# sens_less_blmd.net
KiCad netlist of a schematic drawn in EAGLE
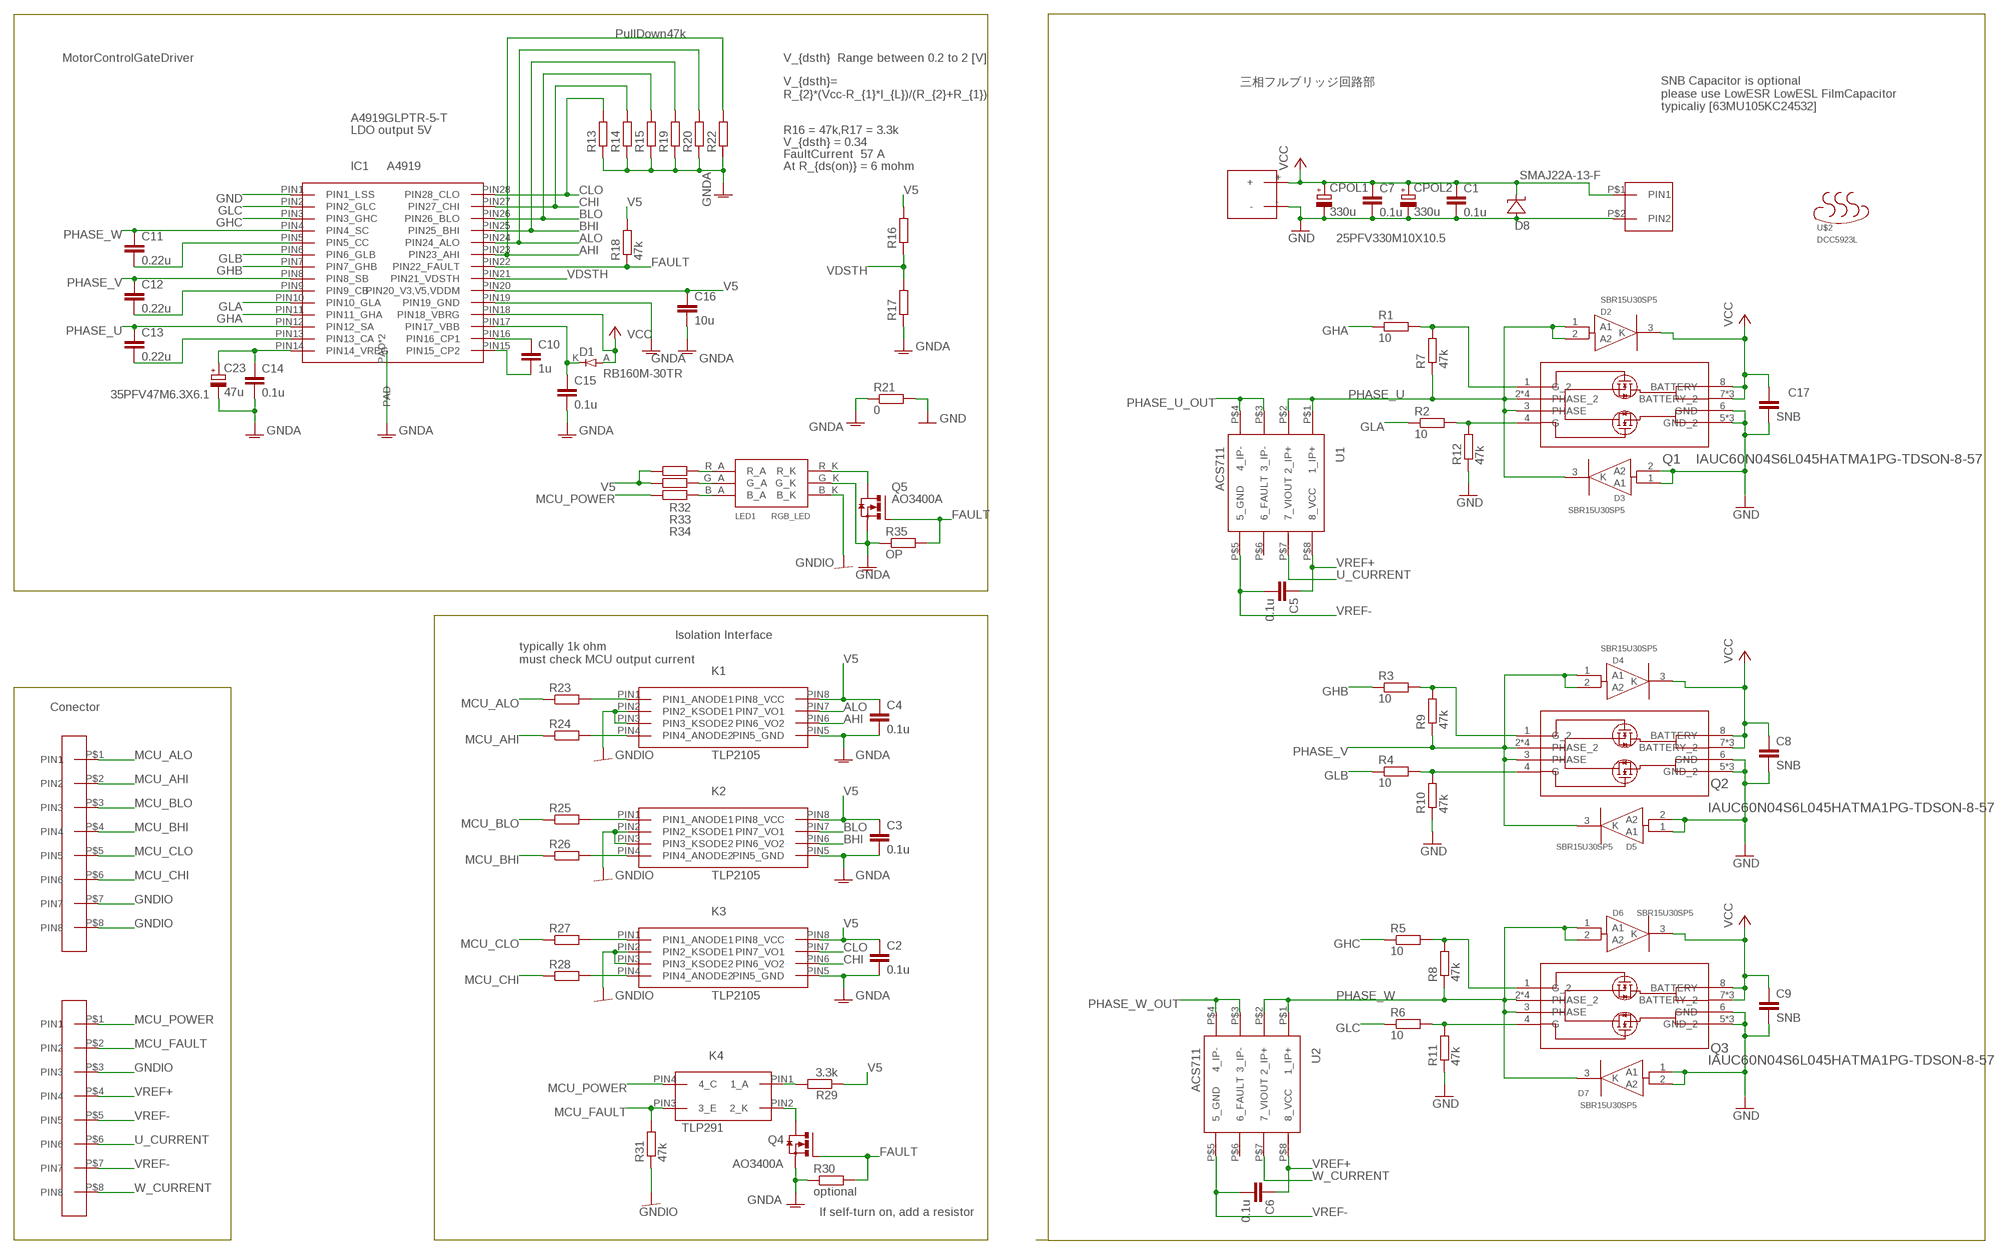
[diagram p0: schematic, sheet 1]

(export (version "E")
  (design (tool "Eeschema 10.0.6"))
  (components
    (comp (ref "C1")
      (value "0.1u")
      (footprint "eagle-import:C1608")
      (libsource (lib "eagle-import") (part "C-EUC1608"))
    )
    (comp (ref "C2")
      (value "0.1u")
      (footprint "eagle-import:C1608")
      (libsource (lib "eagle-import") (part "C-EUC1608"))
    )
    (comp (ref "C3")
      (value "0.1u")
      (footprint "eagle-import:C1608")
      (libsource (lib "eagle-import") (part "C-EUC1608"))
    )
    (comp (ref "C4")
      (value "0.1u")
      (footprint "eagle-import:C1608")
      (libsource (lib "eagle-import") (part "C-EUC1608"))
    )
    (comp (ref "C5")
      (value "0.1u")
      (footprint "eagle-import:C1608")
      (libsource (lib "eagle-import") (part "C-EUC1608"))
    )
    (comp (ref "C6")
      (value "0.1u")
      (footprint "eagle-import:C1608")
      (libsource (lib "eagle-import") (part "C-EUC1608"))
    )
    (comp (ref "C7")
      (value "0.1u")
      (footprint "eagle-import:C1608")
      (libsource (lib "eagle-import") (part "C-EUC1608"))
    )
    (comp (ref "C8")
      (value "SNB")
      (footprint "eagle-import:C4532")
      (libsource (lib "eagle-import") (part "C-EUC4532"))
    )
    (comp (ref "C9")
      (value "SNB")
      (footprint "eagle-import:C4532")
      (libsource (lib "eagle-import") (part "C-EUC4532"))
    )
    (comp (ref "C10")
      (value "1u")
      (footprint "eagle-import:C1608")
      (libsource (lib "eagle-import") (part "C-EUC1608"))
    )
    (comp (ref "C11")
      (value "0.22u")
      (footprint "eagle-import:C1608")
      (libsource (lib "eagle-import") (part "C-EUC1608"))
    )
    (comp (ref "C12")
      (value "0.22u")
      (footprint "eagle-import:C1608")
      (libsource (lib "eagle-import") (part "C-EUC1608"))
    )
    (comp (ref "C13")
      (value "0.22u")
      (footprint "eagle-import:C1608")
      (libsource (lib "eagle-import") (part "C-EUC1608"))
    )
    (comp (ref "C14")
      (value "0.1u")
      (footprint "eagle-import:C1608")
      (libsource (lib "eagle-import") (part "C-EUC1608"))
    )
    (comp (ref "C15")
      (value "0.1u")
      (footprint "eagle-import:C1608")
      (libsource (lib "eagle-import") (part "C-EUC1608"))
    )
    (comp (ref "C16")
      (value "10u")
      (footprint "eagle-import:C1608")
      (libsource (lib "eagle-import") (part "C-EUC1608"))
    )
    (comp (ref "C17")
      (value "SNB")
      (footprint "eagle-import:C4532")
      (libsource (lib "eagle-import") (part "C-EUC4532"))
    )
    (comp (ref "C23")
      (value "47u")
      (footprint "eagle-import:153CLV-0605")
      (libsource (lib "eagle-import") (part "CPOL-EU153CLV-0605"))
    )
    (comp (ref "CON1")
      (value "XH_8P")
      (footprint "eagle-import:XH_8P")
      (libsource (lib "eagle-import") (part "XH_8P"))
    )
    (comp (ref "CON2")
      (value "XH_8P")
      (footprint "eagle-import:XH_8P")
      (libsource (lib "eagle-import") (part "XH_8P"))
    )
    (comp (ref "CPOL1")
      (value "330u")
      (footprint "eagle-import:1014CAPA")
      (libsource (lib "eagle-import") (part "C_DEKAI"))
    )
    (comp (ref "CPOL2")
      (value "330u")
      (footprint "eagle-import:1014CAPA")
      (libsource (lib "eagle-import") (part "C_DEKAI"))
    )
    (comp (ref "D1")
      (value "RB160M-30TR")
      (footprint "eagle-import:SOD_123")
      (libsource (lib "eagle-import") (part "SMD_DAIOD"))
    )
    (comp (ref "D2")
      (value "SBR15U30SP5")
      (footprint "eagle-import:POWERDI_5")
      (libsource (lib "eagle-import") (part "SBR15U30SP5"))
    )
    (comp (ref "D3")
      (value "SBR15U30SP5")
      (footprint "eagle-import:POWERDI_5")
      (libsource (lib "eagle-import") (part "SBR15U30SP5"))
    )
    (comp (ref "D4")
      (value "SBR15U30SP5")
      (footprint "eagle-import:POWERDI_5")
      (libsource (lib "eagle-import") (part "SBR15U30SP5"))
    )
    (comp (ref "D5")
      (value "SBR15U30SP5")
      (footprint "eagle-import:POWERDI_5")
      (libsource (lib "eagle-import") (part "SBR15U30SP5"))
    )
    (comp (ref "D6")
      (value "SBR15U30SP5")
      (footprint "eagle-import:POWERDI_5")
      (libsource (lib "eagle-import") (part "SBR15U30SP5"))
    )
    (comp (ref "D7")
      (value "SBR15U30SP5")
      (footprint "eagle-import:POWERDI_5")
      (libsource (lib "eagle-import") (part "SBR15U30SP5"))
    )
    (comp (ref "D8")
      (value "SMAJ22A-13-F")
      (footprint "eagle-import:DO-214AC")
      (libsource (lib "eagle-import") (part "SMAJ22A-13-F"))
    )
    (comp (ref "IC1")
      (value "A4919")
      (footprint "eagle-import:TSSOP_28P_ALLEGRO_E")
      (libsource (lib "eagle-import") (part "A4919"))
    )
    (comp (ref "K1")
      (value "TLP2105")
      (footprint "eagle-import:SOP8")
      (libsource (lib "eagle-import") (part "TLP2105"))
    )
    (comp (ref "K2")
      (value "TLP2105")
      (footprint "eagle-import:SOP8")
      (libsource (lib "eagle-import") (part "TLP2105"))
    )
    (comp (ref "K3")
      (value "TLP2105")
      (footprint "eagle-import:SOP8")
      (libsource (lib "eagle-import") (part "TLP2105"))
    )
    (comp (ref "K4")
      (value "TLP291")
      (footprint "eagle-import:TLP291")
      (libsource (lib "eagle-import") (part "TLP291"))
    )
    (comp (ref "LED1")
      (value "RGB_LED")
      (footprint "eagle-import:RGB_LED")
      (libsource (lib "eagle-import") (part "RGB_LED"))
    )
    (comp (ref "Q1")
      (value "IAUC60N04S6L045HATMA1PG-TDSON-8-57")
      (footprint "eagle-import:PG-TDSON-8-57")
      (fields
        (field (name "MANUFACTURER_PART_NUMBER") "IAUC60N04S6L045HATMA1")
        (field (name "COPYRIGHT") "Copyright (C) 2024 Ultra Librarian. All rights reserved.")
      )
      (libsource (lib "eagle-import") (part "IAUC60N04S6L045HATMA1PG-TDSON-8-57"))
    )
    (comp (ref "Q2")
      (value "IAUC60N04S6L045HATMA1PG-TDSON-8-57")
      (footprint "eagle-import:PG-TDSON-8-57")
      (fields
        (field (name "MANUFACTURER_PART_NUMBER") "IAUC60N04S6L045HATMA1")
        (field (name "COPYRIGHT") "Copyright (C) 2024 Ultra Librarian. All rights reserved.")
      )
      (libsource (lib "eagle-import") (part "IAUC60N04S6L045HATMA1PG-TDSON-8-57"))
    )
    (comp (ref "Q3")
      (value "IAUC60N04S6L045HATMA1PG-TDSON-8-57")
      (footprint "eagle-import:PG-TDSON-8-57")
      (fields
        (field (name "MANUFACTURER_PART_NUMBER") "IAUC60N04S6L045HATMA1")
        (field (name "COPYRIGHT") "Copyright (C) 2024 Ultra Librarian. All rights reserved.")
      )
      (libsource (lib "eagle-import") (part "IAUC60N04S6L045HATMA1PG-TDSON-8-57"))
    )
    (comp (ref "Q4")
      (value "AO3400A")
      (footprint "eagle-import:SOT23")
      (libsource (lib "eagle-import") (part "SOT23_NFET"))
    )
    (comp (ref "Q5")
      (value "AO3400A")
      (footprint "eagle-import:SOT23")
      (libsource (lib "eagle-import") (part "SOT23_NFET"))
    )
    (comp (ref "R1")
      (value "10")
      (footprint "eagle-import:1608")
      (libsource (lib "eagle-import") (part "R_REG"))
    )
    (comp (ref "R2")
      (value "10")
      (footprint "eagle-import:1608")
      (libsource (lib "eagle-import") (part "R_REG"))
    )
    (comp (ref "R3")
      (value "10")
      (footprint "eagle-import:1608")
      (libsource (lib "eagle-import") (part "R_REG"))
    )
    (comp (ref "R4")
      (value "10")
      (footprint "eagle-import:1608")
      (libsource (lib "eagle-import") (part "R_REG"))
    )
    (comp (ref "R5")
      (value "10")
      (footprint "eagle-import:1608")
      (libsource (lib "eagle-import") (part "R_REG"))
    )
    (comp (ref "R6")
      (value "10")
      (footprint "eagle-import:1608")
      (libsource (lib "eagle-import") (part "R_REG"))
    )
    (comp (ref "R7")
      (value "47k")
      (footprint "eagle-import:1608")
      (libsource (lib "eagle-import") (part "R_REG"))
    )
    (comp (ref "R8")
      (value "47k")
      (footprint "eagle-import:1608")
      (libsource (lib "eagle-import") (part "R_REG"))
    )
    (comp (ref "R9")
      (value "47k")
      (footprint "eagle-import:1608")
      (libsource (lib "eagle-import") (part "R_REG"))
    )
    (comp (ref "R10")
      (value "47k")
      (footprint "eagle-import:1608")
      (libsource (lib "eagle-import") (part "R_REG"))
    )
    (comp (ref "R11")
      (value "47k")
      (footprint "eagle-import:1608")
      (libsource (lib "eagle-import") (part "R_REG"))
    )
    (comp (ref "R12")
      (value "47k")
      (footprint "eagle-import:1608")
      (libsource (lib "eagle-import") (part "R_REG"))
    )
    (comp (ref "R13")
      (value "R_REG")
      (footprint "eagle-import:1608")
      (libsource (lib "eagle-import") (part "R_REG"))
    )
    (comp (ref "R14")
      (value "R_REG")
      (footprint "eagle-import:1608")
      (libsource (lib "eagle-import") (part "R_REG"))
    )
    (comp (ref "R15")
      (value "R_REG")
      (footprint "eagle-import:1608")
      (libsource (lib "eagle-import") (part "R_REG"))
    )
    (comp (ref "R16")
      (value "R_REG")
      (footprint "eagle-import:1608")
      (libsource (lib "eagle-import") (part "R_REG"))
    )
    (comp (ref "R17")
      (value "R_REG")
      (footprint "eagle-import:1608")
      (libsource (lib "eagle-import") (part "R_REG"))
    )
    (comp (ref "R18")
      (value "47k")
      (footprint "eagle-import:1608")
      (libsource (lib "eagle-import") (part "R_REG"))
    )
    (comp (ref "R19")
      (value "R_REG")
      (footprint "eagle-import:1608")
      (libsource (lib "eagle-import") (part "R_REG"))
    )
    (comp (ref "R20")
      (value "R_REG")
      (footprint "eagle-import:1608")
      (libsource (lib "eagle-import") (part "R_REG"))
    )
    (comp (ref "R21")
      (value "0")
      (footprint "eagle-import:1608")
      (libsource (lib "eagle-import") (part "R_REG"))
    )
    (comp (ref "R22")
      (value "R_REG")
      (footprint "eagle-import:1608")
      (libsource (lib "eagle-import") (part "R_REG"))
    )
    (comp (ref "R23")
      (value "R_REG")
      (footprint "eagle-import:1608")
      (libsource (lib "eagle-import") (part "R_REG"))
    )
    (comp (ref "R24")
      (value "R_REG")
      (footprint "eagle-import:1608")
      (libsource (lib "eagle-import") (part "R_REG"))
    )
    (comp (ref "R25")
      (value "R_REG")
      (footprint "eagle-import:1608")
      (libsource (lib "eagle-import") (part "R_REG"))
    )
    (comp (ref "R26")
      (value "R_REG")
      (footprint "eagle-import:1608")
      (libsource (lib "eagle-import") (part "R_REG"))
    )
    (comp (ref "R27")
      (value "R_REG")
      (footprint "eagle-import:1608")
      (libsource (lib "eagle-import") (part "R_REG"))
    )
    (comp (ref "R28")
      (value "R_REG")
      (footprint "eagle-import:1608")
      (libsource (lib "eagle-import") (part "R_REG"))
    )
    (comp (ref "R29")
      (value "3.3k")
      (footprint "eagle-import:1608")
      (libsource (lib "eagle-import") (part "R_REG"))
    )
    (comp (ref "R30")
      (value "optional")
      (footprint "eagle-import:1608")
      (libsource (lib "eagle-import") (part "R_REG"))
    )
    (comp (ref "R31")
      (value "47k")
      (footprint "eagle-import:1608")
      (libsource (lib "eagle-import") (part "R_REG"))
    )
    (comp (ref "R32")
      (value "R_REG")
      (footprint "eagle-import:1608")
      (libsource (lib "eagle-import") (part "R_REG"))
    )
    (comp (ref "R33")
      (value "R_REG")
      (footprint "eagle-import:1608")
      (libsource (lib "eagle-import") (part "R_REG"))
    )
    (comp (ref "R34")
      (value "R_REG")
      (footprint "eagle-import:1608")
      (libsource (lib "eagle-import") (part "R_REG"))
    )
    (comp (ref "R35")
      (value "OP")
      (footprint "eagle-import:1608")
      (libsource (lib "eagle-import") (part "R_REG"))
    )
    (comp (ref "U$1")
      (value "XH_2P")
      (footprint "eagle-import:XH_2P")
      (libsource (lib "eagle-import") (part "XH_2P"))
    )
    (comp (ref "U$2")
      (value "DCC5923L")
      (footprint "eagle-import:DCC5923L")
      (libsource (lib "eagle-import") (part "DCC5923L"))
    )
    (comp (ref "U$22")
      (value "XT60")
      (footprint "eagle-import:XT60")
      (libsource (lib "eagle-import") (part "XT60"))
    )
    (comp (ref "U1")
      (value "ACS711")
      (footprint "eagle-import:SOIC8")
      (libsource (lib "eagle-import") (part "ACS711"))
    )
    (comp (ref "U2")
      (value "ACS711")
      (footprint "eagle-import:SOIC8")
      (libsource (lib "eagle-import") (part "ACS711"))
    )
  )
  (nets
    (net (code "1") (name "/AHI") (class "Default")
      (node (ref "IC1") (pin "PIN23") (pinfunction "PIN23_AHI_PIN23") (pintype "bidirectional"))
      (node (ref "K1") (pin "PIN6") (pinfunction "PIN6_VO2_PIN6") (pintype "bidirectional"))
      (node (ref "R22") (pin "2") (pinfunction "2_2") (pintype "passive"))
    )
    (net (code "2") (name "/ALO") (class "Default")
      (node (ref "IC1") (pin "PIN24") (pinfunction "PIN24_ALO_PIN24") (pintype "bidirectional"))
      (node (ref "K1") (pin "PIN7") (pinfunction "PIN7_VO1_PIN7") (pintype "bidirectional"))
      (node (ref "R20") (pin "2") (pinfunction "2_2") (pintype "passive"))
    )
    (net (code "3") (name "/BHI") (class "Default")
      (node (ref "IC1") (pin "PIN25") (pinfunction "PIN25_BHI_PIN25") (pintype "bidirectional"))
      (node (ref "K2") (pin "PIN6") (pinfunction "PIN6_VO2_PIN6") (pintype "bidirectional"))
      (node (ref "R19") (pin "2") (pinfunction "2_2") (pintype "passive"))
    )
    (net (code "4") (name "/BLO") (class "Default")
      (node (ref "IC1") (pin "PIN26") (pinfunction "PIN26_BLO_PIN26") (pintype "bidirectional"))
      (node (ref "K2") (pin "PIN7") (pinfunction "PIN7_VO1_PIN7") (pintype "bidirectional"))
      (node (ref "R15") (pin "2") (pinfunction "2_2") (pintype "passive"))
    )
    (net (code "5") (name "/CHI") (class "Default")
      (node (ref "IC1") (pin "PIN27") (pinfunction "PIN27_CHI_PIN27") (pintype "bidirectional"))
      (node (ref "K3") (pin "PIN6") (pinfunction "PIN6_VO2_PIN6") (pintype "bidirectional"))
      (node (ref "R14") (pin "2") (pinfunction "2_2") (pintype "passive"))
    )
    (net (code "6") (name "/CLO") (class "Default")
      (node (ref "IC1") (pin "PIN28") (pinfunction "PIN28_CLO_PIN28") (pintype "bidirectional"))
      (node (ref "K3") (pin "PIN7") (pinfunction "PIN7_VO1_PIN7") (pintype "bidirectional"))
      (node (ref "R13") (pin "2") (pinfunction "2_2") (pintype "passive"))
    )
    (net (code "7") (name "/FAULT") (class "Default")
      (node (ref "IC1") (pin "PIN22") (pinfunction "PIN22_FAULT_PIN22") (pintype "bidirectional"))
      (node (ref "Q4") (pin "PIN1") (pinfunction "PIN1_G_PIN1") (pintype "passive"))
      (node (ref "Q5") (pin "PIN1") (pinfunction "PIN1_G_PIN1") (pintype "passive"))
      (node (ref "R18") (pin "1") (pinfunction "1_1") (pintype "passive"))
      (node (ref "R30") (pin "2") (pinfunction "2_2") (pintype "passive"))
      (node (ref "R35") (pin "2") (pinfunction "2_2") (pintype "passive"))
    )
    (net (code "8") (name "/GHA") (class "Default")
      (node (ref "IC1") (pin "PIN11") (pinfunction "PIN11_GHA_PIN11") (pintype "bidirectional"))
      (node (ref "R1") (pin "1") (pinfunction "1_1") (pintype "passive"))
    )
    (net (code "9") (name "/GHB") (class "Default")
      (node (ref "IC1") (pin "PIN7") (pinfunction "PIN7_GHB_PIN7") (pintype "bidirectional"))
      (node (ref "R3") (pin "1") (pinfunction "1_1") (pintype "passive"))
    )
    (net (code "10") (name "/GHC") (class "Default")
      (node (ref "IC1") (pin "PIN3") (pinfunction "PIN3_GHC_PIN3") (pintype "bidirectional"))
      (node (ref "R5") (pin "1") (pinfunction "1_1") (pintype "passive"))
    )
    (net (code "11") (name "/GLA") (class "Default")
      (node (ref "IC1") (pin "PIN10") (pinfunction "PIN10_GLA_PIN10") (pintype "bidirectional"))
      (node (ref "R2") (pin "1") (pinfunction "1_1") (pintype "passive"))
    )
    (net (code "12") (name "/GLB") (class "Default")
      (node (ref "IC1") (pin "PIN6") (pinfunction "PIN6_GLB_PIN6") (pintype "bidirectional"))
      (node (ref "R4") (pin "1") (pinfunction "1_1") (pintype "passive"))
    )
    (net (code "13") (name "/GLC") (class "Default")
      (node (ref "IC1") (pin "PIN2") (pinfunction "PIN2_GLC_PIN2") (pintype "bidirectional"))
      (node (ref "R6") (pin "1") (pinfunction "1_1") (pintype "passive"))
    )
    (net (code "14") (name "/MCU_AHI") (class "Default")
      (node (ref "CON2") (pin "P$2") (pinfunction "PIN2_P$2") (pintype "bidirectional"))
      (node (ref "R24") (pin "1") (pinfunction "1_1") (pintype "passive"))
    )
    (net (code "15") (name "/MCU_ALO") (class "Default")
      (node (ref "CON2") (pin "P$1") (pinfunction "PIN1_P$1") (pintype "bidirectional"))
      (node (ref "R23") (pin "1") (pinfunction "1_1") (pintype "passive"))
    )
    (net (code "16") (name "/MCU_BHI") (class "Default")
      (node (ref "CON2") (pin "P$4") (pinfunction "PIN4_P$4") (pintype "bidirectional"))
      (node (ref "R26") (pin "1") (pinfunction "1_1") (pintype "passive"))
    )
    (net (code "17") (name "/MCU_BLO") (class "Default")
      (node (ref "CON2") (pin "P$3") (pinfunction "PIN3_P$3") (pintype "bidirectional"))
      (node (ref "R25") (pin "1") (pinfunction "1_1") (pintype "passive"))
    )
    (net (code "18") (name "/MCU_CHI") (class "Default")
      (node (ref "CON2") (pin "P$6") (pinfunction "PIN6_P$6") (pintype "bidirectional"))
      (node (ref "R28") (pin "1") (pinfunction "1_1") (pintype "passive"))
    )
    (net (code "19") (name "/MCU_CLO") (class "Default")
      (node (ref "CON2") (pin "P$5") (pinfunction "PIN5_P$5") (pintype "bidirectional"))
      (node (ref "R27") (pin "1") (pinfunction "1_1") (pintype "passive"))
    )
    (net (code "20") (name "/MCU_FAULT") (class "Default")
      (node (ref "CON1") (pin "P$2") (pinfunction "PIN2_P$2") (pintype "bidirectional"))
      (node (ref "K4") (pin "PIN3") (pinfunction "3_E_PIN3") (pintype "bidirectional"))
      (node (ref "R31") (pin "2") (pinfunction "2_2") (pintype "passive"))
    )
    (net (code "21") (name "/MCU_POWER") (class "Default")
      (node (ref "CON1") (pin "P$1") (pinfunction "PIN1_P$1") (pintype "bidirectional"))
      (node (ref "K4") (pin "PIN4") (pinfunction "4_C_PIN4") (pintype "bidirectional"))
      (node (ref "R34") (pin "1") (pinfunction "1_1") (pintype "passive"))
    )
    (net (code "22") (name "/PHASE_U") (class "Default")
      (node (ref "C13") (pin "1") (pinfunction "1_1") (pintype "passive"))
      (node (ref "D2") (pin "1") (pinfunction "A1_1") (pintype "bidirectional"))
      (node (ref "D2") (pin "2") (pinfunction "A2_2") (pintype "bidirectional"))
      (node (ref "D3") (pin "3") (pinfunction "K_3") (pintype "bidirectional"))
      (node (ref "IC1") (pin "PIN12") (pinfunction "PIN12_SA_PIN12") (pintype "bidirectional"))
      (node (ref "Q1") (pin "2") (pinfunction "PHASE_2_2") (pintype "passive"))
      (node (ref "Q1") (pin "3") (pinfunction "PHASE_3") (pintype "passive"))
      (node (ref "Q1") (pin "SDPAD") (pinfunction "PHASE_2_SDPAD") (pintype "passive"))
      (node (ref "Q1") (pin "SDPAD@1") (pinfunction "PHASE_2_SDPAD@1") (pintype "passive"))
      (node (ref "Q1") (pin "SDPAD@2") (pinfunction "PHASE_2_SDPAD@2") (pintype "passive"))
      (node (ref "R7") (pin "1") (pinfunction "1_1") (pintype "passive"))
      (node (ref "U1") (pin "P$1") (pinfunction "1_IP+_P$1") (pintype "bidirectional"))
      (node (ref "U1") (pin "P$2") (pinfunction "2_IP+_P$2") (pintype "bidirectional"))
    )
    (net (code "23") (name "/PHASE_U_OUT") (class "Default")
      (node (ref "U1") (pin "P$3") (pinfunction "3_IP-_P$3") (pintype "bidirectional"))
      (node (ref "U1") (pin "P$4") (pinfunction "4_IP-_P$4") (pintype "bidirectional"))
    )
    (net (code "24") (name "/PHASE_V") (class "Default")
      (node (ref "C12") (pin "1") (pinfunction "1_1") (pintype "passive"))
      (node (ref "D4") (pin "1") (pinfunction "A1_1") (pintype "bidirectional"))
      (node (ref "D4") (pin "2") (pinfunction "A2_2") (pintype "bidirectional"))
      (node (ref "D5") (pin "3") (pinfunction "K_3") (pintype "bidirectional"))
      (node (ref "IC1") (pin "PIN8") (pinfunction "PIN8_SB_PIN8") (pintype "bidirectional"))
      (node (ref "Q2") (pin "2") (pinfunction "PHASE_2_2") (pintype "passive"))
      (node (ref "Q2") (pin "3") (pinfunction "PHASE_3") (pintype "passive"))
      (node (ref "Q2") (pin "SDPAD") (pinfunction "PHASE_2_SDPAD") (pintype "passive"))
      (node (ref "Q2") (pin "SDPAD@1") (pinfunction "PHASE_2_SDPAD@1") (pintype "passive"))
      (node (ref "Q2") (pin "SDPAD@2") (pinfunction "PHASE_2_SDPAD@2") (pintype "passive"))
      (node (ref "R9") (pin "1") (pinfunction "1_1") (pintype "passive"))
    )
    (net (code "25") (name "/PHASE_W") (class "Default")
      (node (ref "C11") (pin "1") (pinfunction "1_1") (pintype "passive"))
      (node (ref "D6") (pin "1") (pinfunction "A1_1") (pintype "bidirectional"))
      (node (ref "D6") (pin "2") (pinfunction "A2_2") (pintype "bidirectional"))
      (node (ref "D7") (pin "3") (pinfunction "K_3") (pintype "bidirectional"))
      (node (ref "IC1") (pin "PIN4") (pinfunction "PIN4_SC_PIN4") (pintype "bidirectional"))
      (node (ref "Q3") (pin "2") (pinfunction "PHASE_2_2") (pintype "passive"))
      (node (ref "Q3") (pin "3") (pinfunction "PHASE_3") (pintype "passive"))
      (node (ref "Q3") (pin "SDPAD") (pinfunction "PHASE_2_SDPAD") (pintype "passive"))
      (node (ref "Q3") (pin "SDPAD@1") (pinfunction "PHASE_2_SDPAD@1") (pintype "passive"))
      (node (ref "Q3") (pin "SDPAD@2") (pinfunction "PHASE_2_SDPAD@2") (pintype "passive"))
      (node (ref "R8") (pin "1") (pinfunction "1_1") (pintype "passive"))
      (node (ref "U2") (pin "P$1") (pinfunction "1_IP+_P$1") (pintype "bidirectional"))
      (node (ref "U2") (pin "P$2") (pinfunction "2_IP+_P$2") (pintype "bidirectional"))
    )
    (net (code "26") (name "/PHASE_W_OUT") (class "Default")
      (node (ref "U2") (pin "P$3") (pinfunction "3_IP-_P$3") (pintype "bidirectional"))
      (node (ref "U2") (pin "P$4") (pinfunction "4_IP-_P$4") (pintype "bidirectional"))
    )
    (net (code "27") (name "/U_CURRENT") (class "Default")
      (node (ref "CON1") (pin "P$6") (pinfunction "PIN6_P$6") (pintype "bidirectional"))
      (node (ref "U1") (pin "P$7") (pinfunction "7_VIOUT_P$7") (pintype "bidirectional"))
    )
    (net (code "28") (name "/V5") (class "Default")
      (node (ref "C16") (pin "1") (pinfunction "1_1") (pintype "passive"))
      (node (ref "C2") (pin "1") (pinfunction "1_1") (pintype "passive"))
      (node (ref "C3") (pin "1") (pinfunction "1_1") (pintype "passive"))
      (node (ref "C4") (pin "1") (pinfunction "1_1") (pintype "passive"))
      (node (ref "IC1") (pin "PIN20") (pinfunction "PIN20_V3,V5,VDDM_PIN20") (pintype "bidirectional"))
      (node (ref "K1") (pin "PIN8") (pinfunction "PIN8_VCC_PIN8") (pintype "bidirectional"))
      (node (ref "K2") (pin "PIN8") (pinfunction "PIN8_VCC_PIN8") (pintype "bidirectional"))
      (node (ref "K3") (pin "PIN8") (pinfunction "PIN8_VCC_PIN8") (pintype "bidirectional"))
      (node (ref "R16") (pin "2") (pinfunction "2_2") (pintype "passive"))
      (node (ref "R18") (pin "2") (pinfunction "2_2") (pintype "passive"))
      (node (ref "R29") (pin "1") (pinfunction "1_1") (pintype "passive"))
      (node (ref "R32") (pin "1") (pinfunction "1_1") (pintype "passive"))
      (node (ref "R33") (pin "1") (pinfunction "1_1") (pintype "passive"))
    )
    (net (code "29") (name "/VDSTH") (class "Default")
      (node (ref "IC1") (pin "PIN21") (pinfunction "PIN21_VDSTH_PIN21") (pintype "bidirectional"))
      (node (ref "R16") (pin "1") (pinfunction "1_1") (pintype "passive"))
      (node (ref "R17") (pin "2") (pinfunction "2_2") (pintype "passive"))
    )
    (net (code "30") (name "/VREF+") (class "Default")
      (node (ref "C5") (pin "1") (pinfunction "1_1") (pintype "passive"))
      (node (ref "C6") (pin "1") (pinfunction "1_1") (pintype "passive"))
      (node (ref "CON1") (pin "P$4") (pinfunction "PIN4_P$4") (pintype "bidirectional"))
      (node (ref "U1") (pin "P$8") (pinfunction "8_VCC_P$8") (pintype "bidirectional"))
      (node (ref "U2") (pin "P$8") (pinfunction "8_VCC_P$8") (pintype "bidirectional"))
    )
    (net (code "31") (name "/VREF-") (class "Default")
      (node (ref "C5") (pin "2") (pinfunction "2_2") (pintype "passive"))
      (node (ref "C6") (pin "2") (pinfunction "2_2") (pintype "passive"))
      (node (ref "CON1") (pin "P$5") (pinfunction "PIN5_P$5") (pintype "bidirectional"))
      (node (ref "CON1") (pin "P$7") (pinfunction "PIN7_P$7") (pintype "bidirectional"))
      (node (ref "U1") (pin "P$5") (pinfunction "5_GND_P$5") (pintype "bidirectional"))
      (node (ref "U2") (pin "P$5") (pinfunction "5_GND_P$5") (pintype "bidirectional"))
    )
    (net (code "32") (name "/W_CURRENT") (class "Default")
      (node (ref "CON1") (pin "P$8") (pinfunction "PIN8_P$8") (pintype "bidirectional"))
      (node (ref "U2") (pin "P$7") (pinfunction "7_VIOUT_P$7") (pintype "bidirectional"))
    )
    (net (code "33") (name "GND") (class "Default")
      (node (ref "C1") (pin "2") (pinfunction "2_2") (pintype "passive"))
      (node (ref "C17") (pin "2") (pinfunction "2_2") (pintype "passive"))
      (node (ref "C7") (pin "2") (pinfunction "2_2") (pintype "passive"))
      (node (ref "C8") (pin "2") (pinfunction "2_2") (pintype "passive"))
      (node (ref "C9") (pin "2") (pinfunction "2_2") (pintype "passive"))
      (node (ref "CPOL1") (pin "-") (pinfunction "-_-") (pintype "passive"))
      (node (ref "CPOL2") (pin "-") (pinfunction "-_-") (pintype "passive"))
      (node (ref "D3") (pin "1") (pinfunction "A1_1") (pintype "bidirectional"))
      (node (ref "D3") (pin "2") (pinfunction "A2_2") (pintype "bidirectional"))
      (node (ref "D5") (pin "1") (pinfunction "A1_1") (pintype "bidirectional"))
      (node (ref "D5") (pin "2") (pinfunction "A2_2") (pintype "bidirectional"))
      (node (ref "D7") (pin "1") (pinfunction "A1_1") (pintype "bidirectional"))
      (node (ref "D7") (pin "2") (pinfunction "A2_2") (pintype "bidirectional"))
      (node (ref "D8") (pin "A") (pinfunction "A_A") (pintype "passive"))
      (node (ref "IC1") (pin "PIN1") (pinfunction "PIN1_LSS_PIN1") (pintype "bidirectional"))
      (node (ref "Q1") (pin "5") (pinfunction "GND_2_5") (pintype "passive"))
      (node (ref "Q1") (pin "6") (pinfunction "GND_6") (pintype "passive"))
      (node (ref "Q1") (pin "SPAD") (pinfunction "GND_2_SPAD") (pintype "passive"))
      (node (ref "Q1") (pin "SPAD@1") (pinfunction "GND_2_SPAD@1") (pintype "passive"))
      (node (ref "Q2") (pin "5") (pinfunction "GND_2_5") (pintype "passive"))
      (node (ref "Q2") (pin "6") (pinfunction "GND_6") (pintype "passive"))
      (node (ref "Q2") (pin "SPAD") (pinfunction "GND_2_SPAD") (pintype "passive"))
      (node (ref "Q2") (pin "SPAD@1") (pinfunction "GND_2_SPAD@1") (pintype "passive"))
      (node (ref "Q3") (pin "5") (pinfunction "GND_2_5") (pintype "passive"))
      (node (ref "Q3") (pin "6") (pinfunction "GND_6") (pintype "passive"))
      (node (ref "Q3") (pin "SPAD") (pinfunction "GND_2_SPAD") (pintype "passive"))
      (node (ref "Q3") (pin "SPAD@1") (pinfunction "GND_2_SPAD@1") (pintype "passive"))
      (node (ref "R10") (pin "1") (pinfunction "1_1") (pintype "passive"))
      (node (ref "R11") (pin "1") (pinfunction "1_1") (pintype "passive"))
      (node (ref "R12") (pin "1") (pinfunction "1_1") (pintype "passive"))
      (node (ref "R21") (pin "2") (pinfunction "2_2") (pintype "passive"))
      (node (ref "U$1") (pin "P$2") (pinfunction "PIN2_P$2") (pintype "bidirectional"))
      (node (ref "U$22") (pin "-") (pinfunction "-_-") (pintype "bidirectional"))
    )
    (net (code "34") (name "GNDA") (class "Default")
      (node (ref "C14") (pin "2") (pinfunction "2_2") (pintype "passive"))
      (node (ref "C15") (pin "2") (pinfunction "2_2") (pintype "passive"))
      (node (ref "C16") (pin "2") (pinfunction "2_2") (pintype "passive"))
      (node (ref "C2") (pin "2") (pinfunction "2_2") (pintype "passive"))
      (node (ref "C23") (pin "-") (pinfunction "-_-") (pintype "passive"))
      (node (ref "C3") (pin "2") (pinfunction "2_2") (pintype "passive"))
      (node (ref "C4") (pin "2") (pinfunction "2_2") (pintype "passive"))
      (node (ref "IC1") (pin "PAD") (pinfunction "PAD_PAD") (pintype "bidirectional"))
      (node (ref "IC1") (pin "PAD@14") (pinfunction "PAD_PAD@14") (pintype "bidirectional"))
      (node (ref "IC1") (pin "PIN19") (pinfunction "PIN19_GND_PIN19") (pintype "bidirectional"))
      (node (ref "K1") (pin "PIN5") (pinfunction "PIN5_GND_PIN5") (pintype "bidirectional"))
      (node (ref "K2") (pin "PIN5") (pinfunction "PIN5_GND_PIN5") (pintype "bidirectional"))
      (node (ref "K3") (pin "PIN5") (pinfunction "PIN5_GND_PIN5") (pintype "bidirectional"))
      (node (ref "LED1") (pin "G_K") (pinfunction "G_K_G_K") (pintype "bidirectional"))
      (node (ref "Q4") (pin "PIN2") (pinfunction "PIN3_S_PIN2") (pintype "passive"))
      (node (ref "Q5") (pin "PIN2") (pinfunction "PIN3_S_PIN2") (pintype "passive"))
      (node (ref "R13") (pin "1") (pinfunction "1_1") (pintype "passive"))
      (node (ref "R14") (pin "1") (pinfunction "1_1") (pintype "passive"))
      (node (ref "R15") (pin "1") (pinfunction "1_1") (pintype "passive"))
      (node (ref "R17") (pin "1") (pinfunction "1_1") (pintype "passive"))
      (node (ref "R19") (pin "1") (pinfunction "1_1") (pintype "passive"))
      (node (ref "R20") (pin "1") (pinfunction "1_1") (pintype "passive"))
      (node (ref "R21") (pin "1") (pinfunction "1_1") (pintype "passive"))
      (node (ref "R22") (pin "1") (pinfunction "1_1") (pintype "passive"))
      (node (ref "R30") (pin "1") (pinfunction "1_1") (pintype "passive"))
      (node (ref "R35") (pin "1") (pinfunction "1_1") (pintype "passive"))
    )
    (net (code "35") (name "GNDIO") (class "Default")
      (node (ref "CON1") (pin "P$3") (pinfunction "PIN3_P$3") (pintype "bidirectional"))
      (node (ref "CON2") (pin "P$7") (pinfunction "PIN7_P$7") (pintype "bidirectional"))
      (node (ref "CON2") (pin "P$8") (pinfunction "PIN8_P$8") (pintype "bidirectional"))
      (node (ref "K1") (pin "PIN2") (pinfunction "PIN2_KSODE1_PIN2") (pintype "bidirectional"))
      (node (ref "K1") (pin "PIN3") (pinfunction "PIN3_KSODE2_PIN3") (pintype "bidirectional"))
      (node (ref "K2") (pin "PIN2") (pinfunction "PIN2_KSODE1_PIN2") (pintype "bidirectional"))
      (node (ref "K2") (pin "PIN3") (pinfunction "PIN3_KSODE2_PIN3") (pintype "bidirectional"))
      (node (ref "K3") (pin "PIN2") (pinfunction "PIN2_KSODE1_PIN2") (pintype "bidirectional"))
      (node (ref "K3") (pin "PIN3") (pinfunction "PIN3_KSODE2_PIN3") (pintype "bidirectional"))
      (node (ref "LED1") (pin "B_K") (pinfunction "B_K_B_K") (pintype "bidirectional"))
      (node (ref "R31") (pin "1") (pinfunction "1_1") (pintype "passive"))
    )
    (net (code "36") (name "Net-(D1-C)") (class "Default")
      (node (ref "C15") (pin "1") (pinfunction "1_1") (pintype "passive"))
      (node (ref "D1") (pin "K") (pinfunction "C_K") (pintype "passive"))
      (node (ref "IC1") (pin "PIN17") (pinfunction "PIN17_VBB_PIN17") (pintype "bidirectional"))
    )
    (net (code "37") (name "Net-(IC1-PIN5_CC)") (class "Default")
      (node (ref "C11") (pin "2") (pinfunction "2_2") (pintype "passive"))
      (node (ref "IC1") (pin "PIN5") (pinfunction "PIN5_CC_PIN5") (pintype "bidirectional"))
    )
    (net (code "38") (name "Net-(IC1-PIN9_CB)") (class "Default")
      (node (ref "C12") (pin "2") (pinfunction "2_2") (pintype "passive"))
      (node (ref "IC1") (pin "PIN9") (pinfunction "PIN9_CB_PIN9") (pintype "bidirectional"))
    )
    (net (code "39") (name "Net-(IC1-PIN13_CA)") (class "Default")
      (node (ref "C13") (pin "2") (pinfunction "2_2") (pintype "passive"))
      (node (ref "IC1") (pin "PIN13") (pinfunction "PIN13_CA_PIN13") (pintype "bidirectional"))
    )
    (net (code "40") (name "Net-(IC1-PIN14_VREG)") (class "Default")
      (node (ref "C14") (pin "1") (pinfunction "1_1") (pintype "passive"))
      (node (ref "C23") (pin "+") (pinfunction "+_+") (pintype "passive"))
      (node (ref "IC1") (pin "PIN14") (pinfunction "PIN14_VREG_PIN14") (pintype "bidirectional"))
    )
    (net (code "41") (name "Net-(IC1-PIN15_CP2)") (class "Default")
      (node (ref "C10") (pin "2") (pinfunction "2_2") (pintype "passive"))
      (node (ref "IC1") (pin "PIN15") (pinfunction "PIN15_CP2_PIN15") (pintype "bidirectional"))
    )
    (net (code "42") (name "Net-(IC1-PIN16_CP1)") (class "Default")
      (node (ref "C10") (pin "1") (pinfunction "1_1") (pintype "passive"))
      (node (ref "IC1") (pin "PIN16") (pinfunction "PIN16_CP1_PIN16") (pintype "bidirectional"))
    )
    (net (code "43") (name "Net-(K1-PIN1_ANODE1)") (class "Default")
      (node (ref "K1") (pin "PIN1") (pinfunction "PIN1_ANODE1_PIN1") (pintype "bidirectional"))
      (node (ref "R23") (pin "2") (pinfunction "2_2") (pintype "passive"))
    )
    (net (code "44") (name "Net-(K1-PIN4_ANODE2)") (class "Default")
      (node (ref "K1") (pin "PIN4") (pinfunction "PIN4_ANODE2_PIN4") (pintype "bidirectional"))
      (node (ref "R24") (pin "2") (pinfunction "2_2") (pintype "passive"))
    )
    (net (code "45") (name "Net-(K2-PIN1_ANODE1)") (class "Default")
      (node (ref "K2") (pin "PIN1") (pinfunction "PIN1_ANODE1_PIN1") (pintype "bidirectional"))
      (node (ref "R25") (pin "2") (pinfunction "2_2") (pintype "passive"))
    )
    (net (code "46") (name "Net-(K2-PIN4_ANODE2)") (class "Default")
      (node (ref "K2") (pin "PIN4") (pinfunction "PIN4_ANODE2_PIN4") (pintype "bidirectional"))
      (node (ref "R26") (pin "2") (pinfunction "2_2") (pintype "passive"))
    )
    (net (code "47") (name "Net-(K3-PIN1_ANODE1)") (class "Default")
      (node (ref "K3") (pin "PIN1") (pinfunction "PIN1_ANODE1_PIN1") (pintype "bidirectional"))
      (node (ref "R27") (pin "2") (pinfunction "2_2") (pintype "passive"))
    )
    (net (code "48") (name "Net-(K3-PIN4_ANODE2)") (class "Default")
      (node (ref "K3") (pin "PIN4") (pinfunction "PIN4_ANODE2_PIN4") (pintype "bidirectional"))
      (node (ref "R28") (pin "2") (pinfunction "2_2") (pintype "passive"))
    )
    (net (code "49") (name "Net-(K4-1_A)") (class "Default")
      (node (ref "K4") (pin "PIN1") (pinfunction "1_A_PIN1") (pintype "bidirectional"))
      (node (ref "R29") (pin "2") (pinfunction "2_2") (pintype "passive"))
    )
    (net (code "50") (name "Net-(K4-2_K)") (class "Default")
      (node (ref "K4") (pin "PIN2") (pinfunction "2_K_PIN2") (pintype "bidirectional"))
      (node (ref "Q4") (pin "PIN3") (pinfunction "PIN2_D_PIN3") (pintype "passive"))
    )
    (net (code "51") (name "Net-(LED1-PadB_A)") (class "Default")
      (node (ref "LED1") (pin "B_A") (pinfunction "B_A_B_A") (pintype "bidirectional"))
      (node (ref "R34") (pin "2") (pinfunction "2_2") (pintype "passive"))
    )
    (net (code "52") (name "Net-(LED1-PadG_A)") (class "Default")
      (node (ref "LED1") (pin "G_A") (pinfunction "G_A_G_A") (pintype "bidirectional"))
      (node (ref "R33") (pin "2") (pinfunction "2_2") (pintype "passive"))
    )
    (net (code "53") (name "Net-(LED1-PadR_A)") (class "Default")
      (node (ref "LED1") (pin "R_A") (pinfunction "R_A_R_A") (pintype "bidirectional"))
      (node (ref "R32") (pin "2") (pinfunction "2_2") (pintype "passive"))
    )
    (net (code "54") (name "Net-(Q1-G)") (class "Default")
      (node (ref "Q1") (pin "4") (pinfunction "G_4") (pintype "passive"))
      (node (ref "R12") (pin "2") (pinfunction "2_2") (pintype "passive"))
      (node (ref "R2") (pin "2") (pinfunction "2_2") (pintype "passive"))
    )
    (net (code "55") (name "Net-(Q1-G_2)") (class "Default")
      (node (ref "Q1") (pin "1") (pinfunction "G_2_1") (pintype "passive"))
      (node (ref "R1") (pin "2") (pinfunction "2_2") (pintype "passive"))
      (node (ref "R7") (pin "2") (pinfunction "2_2") (pintype "passive"))
    )
    (net (code "56") (name "Net-(Q2-G)") (class "Default")
      (node (ref "Q2") (pin "4") (pinfunction "G_4") (pintype "passive"))
      (node (ref "R10") (pin "2") (pinfunction "2_2") (pintype "passive"))
      (node (ref "R4") (pin "2") (pinfunction "2_2") (pintype "passive"))
    )
    (net (code "57") (name "Net-(Q2-G_2)") (class "Default")
      (node (ref "Q2") (pin "1") (pinfunction "G_2_1") (pintype "passive"))
      (node (ref "R3") (pin "2") (pinfunction "2_2") (pintype "passive"))
      (node (ref "R9") (pin "2") (pinfunction "2_2") (pintype "passive"))
    )
    (net (code "58") (name "Net-(Q3-G)") (class "Default")
      (node (ref "Q3") (pin "4") (pinfunction "G_4") (pintype "passive"))
      (node (ref "R11") (pin "2") (pinfunction "2_2") (pintype "passive"))
      (node (ref "R6") (pin "2") (pinfunction "2_2") (pintype "passive"))
    )
    (net (code "59") (name "Net-(Q3-G_2)") (class "Default")
      (node (ref "Q3") (pin "1") (pinfunction "G_2_1") (pintype "passive"))
      (node (ref "R5") (pin "2") (pinfunction "2_2") (pintype "passive"))
      (node (ref "R8") (pin "2") (pinfunction "2_2") (pintype "passive"))
    )
    (net (code "60") (name "Net-(Q5-PIN2_D)") (class "Default")
      (node (ref "LED1") (pin "R_K") (pinfunction "R_K_R_K") (pintype "bidirectional"))
      (node (ref "Q5") (pin "PIN3") (pinfunction "PIN2_D_PIN3") (pintype "passive"))
    )
    (net (code "61") (name "VCC") (class "Default")
      (node (ref "C1") (pin "1") (pinfunction "1_1") (pintype "passive"))
      (node (ref "C17") (pin "1") (pinfunction "1_1") (pintype "passive"))
      (node (ref "C7") (pin "1") (pinfunction "1_1") (pintype "passive"))
      (node (ref "C8") (pin "1") (pinfunction "1_1") (pintype "passive"))
      (node (ref "C9") (pin "1") (pinfunction "1_1") (pintype "passive"))
      (node (ref "CPOL1") (pin "+") (pinfunction "+_+") (pintype "passive"))
      (node (ref "CPOL2") (pin "+") (pinfunction "+_+") (pintype "passive"))
      (node (ref "D1") (pin "A") (pinfunction "A_A") (pintype "passive"))
      (node (ref "D2") (pin "3") (pinfunction "K_3") (pintype "bidirectional"))
      (node (ref "D4") (pin "3") (pinfunction "K_3") (pintype "bidirectional"))
      (node (ref "D6") (pin "3") (pinfunction "K_3") (pintype "bidirectional"))
      (node (ref "D8") (pin "C") (pinfunction "C_C") (pintype "passive"))
      (node (ref "IC1") (pin "PIN18") (pinfunction "PIN18_VBRG_PIN18") (pintype "bidirectional"))
      (node (ref "Q1") (pin "7") (pinfunction "BATTERY_2_7") (pintype "passive"))
      (node (ref "Q1") (pin "8") (pinfunction "BATTERY_8") (pintype "passive"))
      (node (ref "Q1") (pin "DPAD") (pinfunction "BATTERY_2_DPAD") (pintype "passive"))
      (node (ref "Q1") (pin "DPAD@1") (pinfunction "BATTERY_2_DPAD@1") (pintype "passive"))
      (node (ref "Q2") (pin "7") (pinfunction "BATTERY_2_7") (pintype "passive"))
      (node (ref "Q2") (pin "8") (pinfunction "BATTERY_8") (pintype "passive"))
      (node (ref "Q2") (pin "DPAD") (pinfunction "BATTERY_2_DPAD") (pintype "passive"))
      (node (ref "Q2") (pin "DPAD@1") (pinfunction "BATTERY_2_DPAD@1") (pintype "passive"))
      (node (ref "Q3") (pin "7") (pinfunction "BATTERY_2_7") (pintype "passive"))
      (node (ref "Q3") (pin "8") (pinfunction "BATTERY_8") (pintype "passive"))
      (node (ref "Q3") (pin "DPAD") (pinfunction "BATTERY_2_DPAD") (pintype "passive"))
      (node (ref "Q3") (pin "DPAD@1") (pinfunction "BATTERY_2_DPAD@1") (pintype "passive"))
      (node (ref "U$1") (pin "P$1") (pinfunction "PIN1_P$1") (pintype "bidirectional"))
      (node (ref "U$22") (pin "+") (pinfunction "+_+") (pintype "bidirectional"))
    )
    (net (code "62") (name "unconnected-(U1-6_FAULT-PadP$6)") (class "Default")
      (node (ref "U1") (pin "P$6") (pinfunction "6_FAULT_P$6") (pintype "bidirectional"))
    )
    (net (code "63") (name "unconnected-(U2-6_FAULT-PadP$6)") (class "Default")
      (node (ref "U2") (pin "P$6") (pinfunction "6_FAULT_P$6") (pintype "bidirectional"))
    )
  )
)
